# R141C.net
KiCad netlist of a schematic drawn in EAGLE
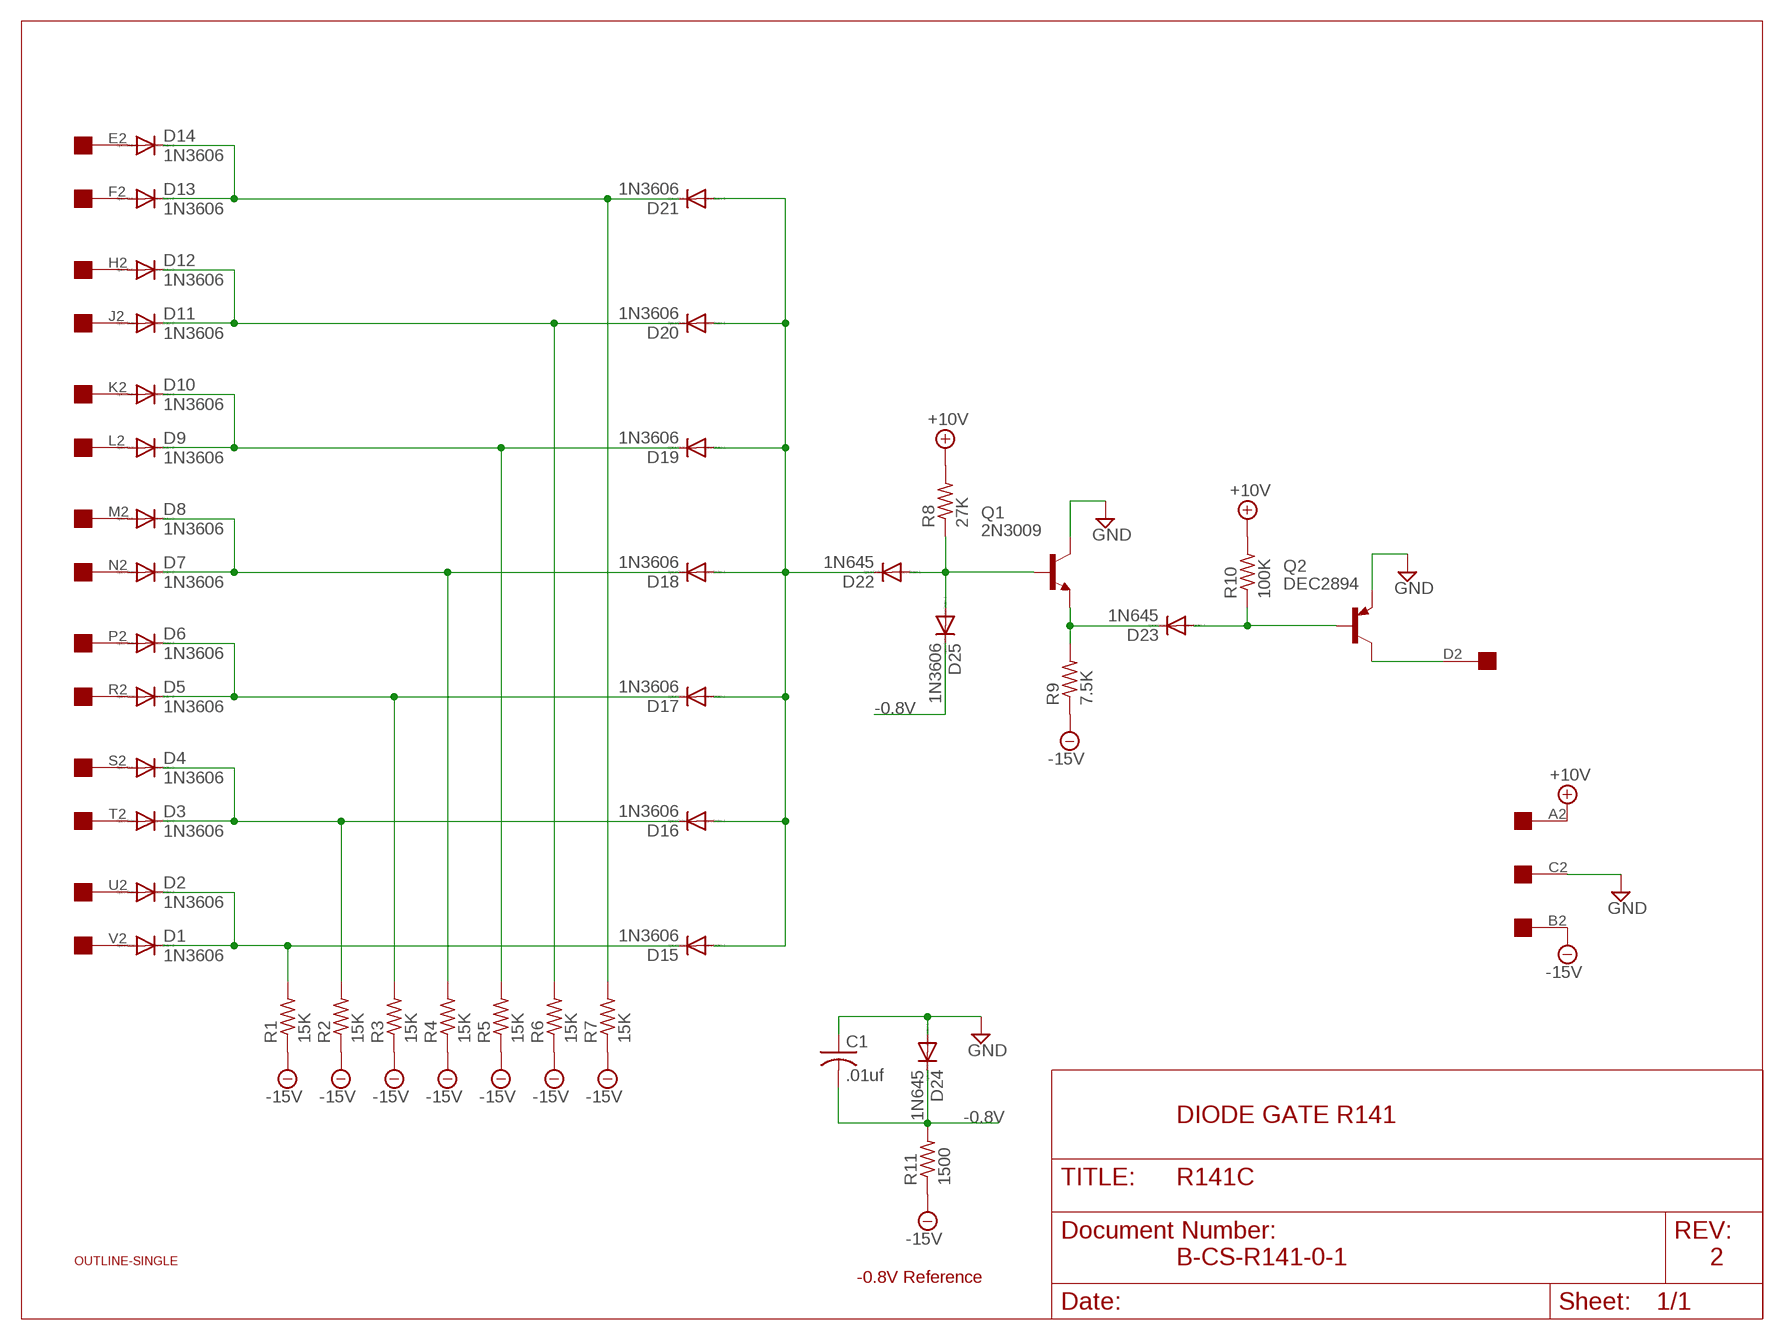
[diagram p0: schematic, sheet 1]

(export (version "E")
  (design (tool "Eeschema 10.0.6"))
  (components
    (comp (ref "C1")
      (value ".01uf")
      (footprint "eagle-import:C063-025X075")
      (libsource (lib "eagle-import") (part "C-US"))
    )
    (comp (ref "D1")
      (value "1N3606")
      (footprint "eagle-import:DO35-10")
      (libsource (lib "eagle-import") (part "1N4148DO35-10"))
    )
    (comp (ref "D2")
      (value "1N3606")
      (footprint "eagle-import:DO35-10")
      (libsource (lib "eagle-import") (part "1N4148DO35-10"))
    )
    (comp (ref "D3")
      (value "1N3606")
      (footprint "eagle-import:DO35-10")
      (libsource (lib "eagle-import") (part "1N4148DO35-10"))
    )
    (comp (ref "D4")
      (value "1N3606")
      (footprint "eagle-import:DO35-10")
      (libsource (lib "eagle-import") (part "1N4148DO35-10"))
    )
    (comp (ref "D5")
      (value "1N3606")
      (footprint "eagle-import:DO35-10")
      (libsource (lib "eagle-import") (part "1N4148DO35-10"))
    )
    (comp (ref "D6")
      (value "1N3606")
      (footprint "eagle-import:DO35-10")
      (libsource (lib "eagle-import") (part "1N4148DO35-10"))
    )
    (comp (ref "D7")
      (value "1N3606")
      (footprint "eagle-import:DO35-10")
      (libsource (lib "eagle-import") (part "1N4148DO35-10"))
    )
    (comp (ref "D8")
      (value "1N3606")
      (footprint "eagle-import:DO35-10")
      (libsource (lib "eagle-import") (part "1N4148DO35-10"))
    )
    (comp (ref "D9")
      (value "1N3606")
      (footprint "eagle-import:DO35-10")
      (libsource (lib "eagle-import") (part "1N4148DO35-10"))
    )
    (comp (ref "D10")
      (value "1N3606")
      (footprint "eagle-import:DO35-10")
      (libsource (lib "eagle-import") (part "1N4148DO35-10"))
    )
    (comp (ref "D11")
      (value "1N3606")
      (footprint "eagle-import:DO35-10")
      (libsource (lib "eagle-import") (part "1N4148DO35-10"))
    )
    (comp (ref "D12")
      (value "1N3606")
      (footprint "eagle-import:DO35-10")
      (libsource (lib "eagle-import") (part "1N4148DO35-10"))
    )
    (comp (ref "D13")
      (value "1N3606")
      (footprint "eagle-import:DO35-10")
      (libsource (lib "eagle-import") (part "1N4148DO35-10"))
    )
    (comp (ref "D14")
      (value "1N3606")
      (footprint "eagle-import:DO35-10")
      (libsource (lib "eagle-import") (part "1N4148DO35-10"))
    )
    (comp (ref "D15")
      (value "1N3606")
      (footprint "eagle-import:DO35-10")
      (libsource (lib "eagle-import") (part "1N4148DO35-10"))
    )
    (comp (ref "D16")
      (value "1N3606")
      (footprint "eagle-import:DO35-10")
      (libsource (lib "eagle-import") (part "1N4148DO35-10"))
    )
    (comp (ref "D17")
      (value "1N3606")
      (footprint "eagle-import:DO35-10")
      (libsource (lib "eagle-import") (part "1N4148DO35-10"))
    )
    (comp (ref "D18")
      (value "1N3606")
      (footprint "eagle-import:DO35-10")
      (libsource (lib "eagle-import") (part "1N4148DO35-10"))
    )
    (comp (ref "D19")
      (value "1N3606")
      (footprint "eagle-import:DO35-10")
      (libsource (lib "eagle-import") (part "1N4148DO35-10"))
    )
    (comp (ref "D20")
      (value "1N3606")
      (footprint "eagle-import:DO35-10")
      (libsource (lib "eagle-import") (part "1N4148DO35-10"))
    )
    (comp (ref "D21")
      (value "1N3606")
      (footprint "eagle-import:DO35-10")
      (libsource (lib "eagle-import") (part "1N4148DO35-10"))
    )
    (comp (ref "D22")
      (value "1N645")
      (footprint "eagle-import:DO35-10")
      (libsource (lib "eagle-import") (part "1N4148DO35-10"))
    )
    (comp (ref "D23")
      (value "1N645")
      (footprint "eagle-import:DO35-10")
      (libsource (lib "eagle-import") (part "1N4148DO35-10"))
    )
    (comp (ref "D24")
      (value "1N645")
      (footprint "eagle-import:DO35-10")
      (libsource (lib "eagle-import") (part "1N4148DO35-10"))
    )
    (comp (ref "D25")
      (value "1N3606")
      (footprint "eagle-import:DO35-10")
      (libsource (lib "eagle-import") (part "1N4148DO35-10"))
    )
    (comp (ref "Q1")
      (value "2N3009")
      (footprint "eagle-import:TO39")
      (libsource (lib "eagle-import") (part "-NPN-TO39-EBC2N3019"))
    )
    (comp (ref "Q2")
      (value "DEC2894")
      (footprint "eagle-import:TO39")
      (libsource (lib "eagle-import") (part "2N3637"))
    )
    (comp (ref "R1")
      (value "15K")
      (footprint "eagle-import:0207_10")
      (libsource (lib "eagle-import") (part "R-US_0207/10"))
    )
    (comp (ref "R2")
      (value "15K")
      (footprint "eagle-import:0207_10")
      (libsource (lib "eagle-import") (part "R-US_0207/10"))
    )
    (comp (ref "R3")
      (value "15K")
      (footprint "eagle-import:0207_10")
      (libsource (lib "eagle-import") (part "R-US_0207/10"))
    )
    (comp (ref "R4")
      (value "15K")
      (footprint "eagle-import:0207_10")
      (libsource (lib "eagle-import") (part "R-US_0207/10"))
    )
    (comp (ref "R5")
      (value "15K")
      (footprint "eagle-import:0207_10")
      (libsource (lib "eagle-import") (part "R-US_0207/10"))
    )
    (comp (ref "R6")
      (value "15K")
      (footprint "eagle-import:0207_10")
      (libsource (lib "eagle-import") (part "R-US_0207/10"))
    )
    (comp (ref "R7")
      (value "15K")
      (footprint "eagle-import:0207_10")
      (libsource (lib "eagle-import") (part "R-US_0207/10"))
    )
    (comp (ref "R8")
      (value "27K")
      (footprint "eagle-import:0207_10")
      (libsource (lib "eagle-import") (part "R-US_0207/10"))
    )
    (comp (ref "R9")
      (value "7.5K")
      (footprint "eagle-import:0207_10")
      (libsource (lib "eagle-import") (part "R-US_0207/10"))
    )
    (comp (ref "R10")
      (value "100K")
      (footprint "eagle-import:0207_10")
      (libsource (lib "eagle-import") (part "R-US_0207/10"))
    )
    (comp (ref "R11")
      (value "1500")
      (footprint "eagle-import:0207_10")
      (libsource (lib "eagle-import") (part "R-US_0207/10"))
    )
    (comp (ref "U$1")
      (value "OUTLINE-SINGLE")
      (footprint "eagle-import:SINGLE")
      (libsource (lib "eagle-import") (part "OUTLINE-SINGLE"))
    )
    (comp (ref "U$2")
      (value "EDGE-1")
      (footprint "eagle-import:EDGE-CON1")
      (libsource (lib "eagle-import") (part "EDGE-1"))
    )
  )
  (nets
    (net (code "1") (name "+10V") (class "Default")
      (node (ref "R10") (pin "2") (pinfunction "2_2") (pintype "passive"))
      (node (ref "R8") (pin "2") (pinfunction "2_2") (pintype "passive"))
      (node (ref "U$2") (pin "A2") (pinfunction "1_A2") (pintype "bidirectional"))
    )
    (net (code "2") (name "-15V") (class "Default")
      (node (ref "R1") (pin "1") (pinfunction "1_1") (pintype "passive"))
      (node (ref "R11") (pin "1") (pinfunction "1_1") (pintype "passive"))
      (node (ref "R2") (pin "1") (pinfunction "1_1") (pintype "passive"))
      (node (ref "R3") (pin "1") (pinfunction "1_1") (pintype "passive"))
      (node (ref "R4") (pin "1") (pinfunction "1_1") (pintype "passive"))
      (node (ref "R5") (pin "1") (pinfunction "1_1") (pintype "passive"))
      (node (ref "R6") (pin "1") (pinfunction "1_1") (pintype "passive"))
      (node (ref "R7") (pin "1") (pinfunction "1_1") (pintype "passive"))
      (node (ref "R9") (pin "1") (pinfunction "1_1") (pintype "passive"))
      (node (ref "U$2") (pin "B2") (pinfunction "1_B2") (pintype "bidirectional"))
    )
    (net (code "3") (name "/-0.8V") (class "Default")
      (node (ref "C1") (pin "2") (pinfunction "2_2") (pintype "passive"))
      (node (ref "D24") (pin "C") (pinfunction "C_C") (pintype "passive"))
      (node (ref "D25") (pin "C") (pinfunction "C_C") (pintype "passive"))
      (node (ref "R11") (pin "2") (pinfunction "2_2") (pintype "passive"))
    )
    (net (code "4") (name "GND") (class "Default")
      (node (ref "C1") (pin "1") (pinfunction "1_1") (pintype "passive"))
      (node (ref "D24") (pin "A") (pinfunction "A_A") (pintype "passive"))
      (node (ref "Q1") (pin "3") (pinfunction "C_3") (pintype "passive"))
      (node (ref "Q2") (pin "1") (pinfunction "E_1") (pintype "passive"))
      (node (ref "U$2") (pin "C2") (pinfunction "1_C2") (pintype "bidirectional"))
    )
    (net (code "5") (name "Net-(D1-PadC)") (class "Default")
      (node (ref "D1") (pin "C") (pinfunction "C_C") (pintype "passive"))
      (node (ref "D15") (pin "C") (pinfunction "C_C") (pintype "passive"))
      (node (ref "D2") (pin "C") (pinfunction "C_C") (pintype "passive"))
      (node (ref "R1") (pin "2") (pinfunction "2_2") (pintype "passive"))
    )
    (net (code "6") (name "Net-(D10-PadC)") (class "Default")
      (node (ref "D10") (pin "C") (pinfunction "C_C") (pintype "passive"))
      (node (ref "D19") (pin "C") (pinfunction "C_C") (pintype "passive"))
      (node (ref "D9") (pin "C") (pinfunction "C_C") (pintype "passive"))
      (node (ref "R5") (pin "2") (pinfunction "2_2") (pintype "passive"))
    )
    (net (code "7") (name "Net-(D11-PadC)") (class "Default")
      (node (ref "D11") (pin "C") (pinfunction "C_C") (pintype "passive"))
      (node (ref "D12") (pin "C") (pinfunction "C_C") (pintype "passive"))
      (node (ref "D20") (pin "C") (pinfunction "C_C") (pintype "passive"))
      (node (ref "R6") (pin "2") (pinfunction "2_2") (pintype "passive"))
    )
    (net (code "8") (name "Net-(D13-PadC)") (class "Default")
      (node (ref "D13") (pin "C") (pinfunction "C_C") (pintype "passive"))
      (node (ref "D14") (pin "C") (pinfunction "C_C") (pintype "passive"))
      (node (ref "D21") (pin "C") (pinfunction "C_C") (pintype "passive"))
      (node (ref "R7") (pin "2") (pinfunction "2_2") (pintype "passive"))
    )
    (net (code "9") (name "Net-(D15-PadA)") (class "Default")
      (node (ref "D15") (pin "A") (pinfunction "A_A") (pintype "passive"))
      (node (ref "D16") (pin "A") (pinfunction "A_A") (pintype "passive"))
      (node (ref "D17") (pin "A") (pinfunction "A_A") (pintype "passive"))
      (node (ref "D18") (pin "A") (pinfunction "A_A") (pintype "passive"))
      (node (ref "D19") (pin "A") (pinfunction "A_A") (pintype "passive"))
      (node (ref "D20") (pin "A") (pinfunction "A_A") (pintype "passive"))
      (node (ref "D21") (pin "A") (pinfunction "A_A") (pintype "passive"))
      (node (ref "D22") (pin "C") (pinfunction "C_C") (pintype "passive"))
    )
    (net (code "10") (name "Net-(D16-PadC)") (class "Default")
      (node (ref "D16") (pin "C") (pinfunction "C_C") (pintype "passive"))
      (node (ref "D3") (pin "C") (pinfunction "C_C") (pintype "passive"))
      (node (ref "D4") (pin "C") (pinfunction "C_C") (pintype "passive"))
      (node (ref "R2") (pin "2") (pinfunction "2_2") (pintype "passive"))
    )
    (net (code "11") (name "Net-(D17-PadC)") (class "Default")
      (node (ref "D17") (pin "C") (pinfunction "C_C") (pintype "passive"))
      (node (ref "D5") (pin "C") (pinfunction "C_C") (pintype "passive"))
      (node (ref "D6") (pin "C") (pinfunction "C_C") (pintype "passive"))
      (node (ref "R3") (pin "2") (pinfunction "2_2") (pintype "passive"))
    )
    (net (code "12") (name "Net-(D18-PadC)") (class "Default")
      (node (ref "D18") (pin "C") (pinfunction "C_C") (pintype "passive"))
      (node (ref "D7") (pin "C") (pinfunction "C_C") (pintype "passive"))
      (node (ref "D8") (pin "C") (pinfunction "C_C") (pintype "passive"))
      (node (ref "R4") (pin "2") (pinfunction "2_2") (pintype "passive"))
    )
    (net (code "13") (name "Net-(Q1-B)") (class "Default")
      (node (ref "D22") (pin "A") (pinfunction "A_A") (pintype "passive"))
      (node (ref "D25") (pin "A") (pinfunction "A_A") (pintype "passive"))
      (node (ref "Q1") (pin "2") (pinfunction "B_2") (pintype "passive"))
      (node (ref "R8") (pin "1") (pinfunction "1_1") (pintype "passive"))
    )
    (net (code "14") (name "Net-(Q1-E)") (class "Default")
      (node (ref "D23") (pin "C") (pinfunction "C_C") (pintype "passive"))
      (node (ref "Q1") (pin "1") (pinfunction "E_1") (pintype "passive"))
      (node (ref "R9") (pin "2") (pinfunction "2_2") (pintype "passive"))
    )
    (net (code "15") (name "Net-(Q2-B)") (class "Default")
      (node (ref "D23") (pin "A") (pinfunction "A_A") (pintype "passive"))
      (node (ref "Q2") (pin "2") (pinfunction "B_2") (pintype "passive"))
      (node (ref "R10") (pin "1") (pinfunction "1_1") (pintype "passive"))
    )
    (net (code "16") (name "Net-(Q2-C)") (class "Default")
      (node (ref "Q2") (pin "3") (pinfunction "C_3") (pintype "passive"))
      (node (ref "U$2") (pin "D2") (pinfunction "1_D2") (pintype "bidirectional"))
    )
    (net (code "17") (name "Net-(U$2E-1)") (class "Default")
      (node (ref "D14") (pin "A") (pinfunction "A_A") (pintype "passive"))
      (node (ref "U$2") (pin "E2") (pinfunction "1_E2") (pintype "bidirectional"))
    )
    (net (code "18") (name "Net-(U$2F-1)") (class "Default")
      (node (ref "D13") (pin "A") (pinfunction "A_A") (pintype "passive"))
      (node (ref "U$2") (pin "F2") (pinfunction "1_F2") (pintype "bidirectional"))
    )
    (net (code "19") (name "Net-(U$2G-1)") (class "Default")
      (node (ref "D12") (pin "A") (pinfunction "A_A") (pintype "passive"))
      (node (ref "U$2") (pin "H2") (pinfunction "1_H2") (pintype "bidirectional"))
    )
    (net (code "20") (name "Net-(U$2H-1)") (class "Default")
      (node (ref "D11") (pin "A") (pinfunction "A_A") (pintype "passive"))
      (node (ref "U$2") (pin "J2") (pinfunction "1_J2") (pintype "bidirectional"))
    )
    (net (code "21") (name "Net-(U$2I-1)") (class "Default")
      (node (ref "D10") (pin "A") (pinfunction "A_A") (pintype "passive"))
      (node (ref "U$2") (pin "K2") (pinfunction "1_K2") (pintype "bidirectional"))
    )
    (net (code "22") (name "Net-(U$2J-1)") (class "Default")
      (node (ref "D9") (pin "A") (pinfunction "A_A") (pintype "passive"))
      (node (ref "U$2") (pin "L2") (pinfunction "1_L2") (pintype "bidirectional"))
    )
    (net (code "23") (name "Net-(U$2K-1)") (class "Default")
      (node (ref "D8") (pin "A") (pinfunction "A_A") (pintype "passive"))
      (node (ref "U$2") (pin "M2") (pinfunction "1_M2") (pintype "bidirectional"))
    )
    (net (code "24") (name "Net-(U$2L-1)") (class "Default")
      (node (ref "D7") (pin "A") (pinfunction "A_A") (pintype "passive"))
      (node (ref "U$2") (pin "N2") (pinfunction "1_N2") (pintype "bidirectional"))
    )
    (net (code "25") (name "Net-(U$2M-1)") (class "Default")
      (node (ref "D6") (pin "A") (pinfunction "A_A") (pintype "passive"))
      (node (ref "U$2") (pin "P2") (pinfunction "1_P2") (pintype "bidirectional"))
    )
    (net (code "26") (name "Net-(U$2N-1)") (class "Default")
      (node (ref "D5") (pin "A") (pinfunction "A_A") (pintype "passive"))
      (node (ref "U$2") (pin "R2") (pinfunction "1_R2") (pintype "bidirectional"))
    )
    (net (code "27") (name "Net-(U$2O-1)") (class "Default")
      (node (ref "D4") (pin "A") (pinfunction "A_A") (pintype "passive"))
      (node (ref "U$2") (pin "S2") (pinfunction "1_S2") (pintype "bidirectional"))
    )
    (net (code "28") (name "Net-(U$2P-1)") (class "Default")
      (node (ref "D3") (pin "A") (pinfunction "A_A") (pintype "passive"))
      (node (ref "U$2") (pin "T2") (pinfunction "1_T2") (pintype "bidirectional"))
    )
    (net (code "29") (name "Net-(U$2Q-1)") (class "Default")
      (node (ref "D2") (pin "A") (pinfunction "A_A") (pintype "passive"))
      (node (ref "U$2") (pin "U2") (pinfunction "1_U2") (pintype "bidirectional"))
    )
    (net (code "30") (name "Net-(U$2R-1)") (class "Default")
      (node (ref "D1") (pin "A") (pinfunction "A_A") (pintype "passive"))
      (node (ref "U$2") (pin "V2") (pinfunction "1_V2") (pintype "bidirectional"))
    )
  )
)
